# JTAG_FPGA_IDC14_2mm.net
KiCad netlist of a schematic drawn in Altium Designer
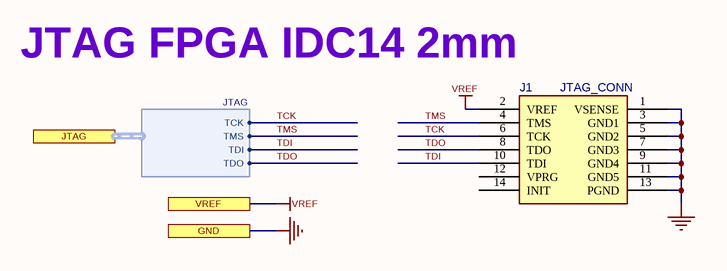
[diagram p0: JTAG_FPGA_IDC14_2mm.SchDoc]

(export (version "E")
  (design (tool "Eeschema 10.0.6"))
  (components
    (comp (ref "J1")
      (value "JTAG_CONN")
      (footprint "IDC2_2X7")
      (description "CONN, JTAG, FPGA, 14P")
      (fields (field (name "MANF") "MOLEX"))
      (libsource (lib "conn_program") (part "CONN_JTAG_FPGA_14"))
    )
  )
  (nets
    (net (code "2") (name "/TCK") (class "Default")
      (node (ref "J1") (pin "6") (pinfunction "TCK_6") (pintype "passive"))
    )
    (net (code "3") (name "/TDI") (class "Default")
      (node (ref "J1") (pin "10") (pinfunction "TDI_10") (pintype "passive"))
    )
    (net (code "4") (name "/TDO") (class "Default")
      (node (ref "J1") (pin "8") (pinfunction "TDO_8") (pintype "passive"))
    )
    (net (code "5") (name "/TMS") (class "Default")
      (node (ref "J1") (pin "4") (pinfunction "TMS_4") (pintype "passive"))
    )
    (net (code "7") (name "GND") (class "Default")
      (node (ref "J1") (pin "1") (pinfunction "VSENSE_1") (pintype "passive"))
      (node (ref "J1") (pin "11") (pinfunction "GND5_11") (pintype "passive"))
      (node (ref "J1") (pin "13") (pinfunction "PGND_13") (pintype "passive"))
      (node (ref "J1") (pin "3") (pinfunction "GND1_3") (pintype "passive"))
      (node (ref "J1") (pin "5") (pinfunction "GND2_5") (pintype "passive"))
      (node (ref "J1") (pin "7") (pinfunction "GND3_7") (pintype "passive"))
      (node (ref "J1") (pin "9") (pinfunction "GND4_9") (pintype "passive"))
    )
    (net (code "8") (name "VREF") (class "Default")
      (node (ref "J1") (pin "2") (pinfunction "VREF_2") (pintype "passive"))
    )
    (net (code "9") (name "unconnected-(J1-INIT-Pad14)") (class "Default")
      (node (ref "J1") (pin "14") (pinfunction "INIT_14") (pintype "passive"))
    )
    (net (code "10") (name "unconnected-(J1-VPRG-Pad12)") (class "Default")
      (node (ref "J1") (pin "12") (pinfunction "VPRG_12") (pintype "passive"))
    )
  )
)
